# PowerPath.net
KiCad netlist of a schematic drawn in Altium Designer
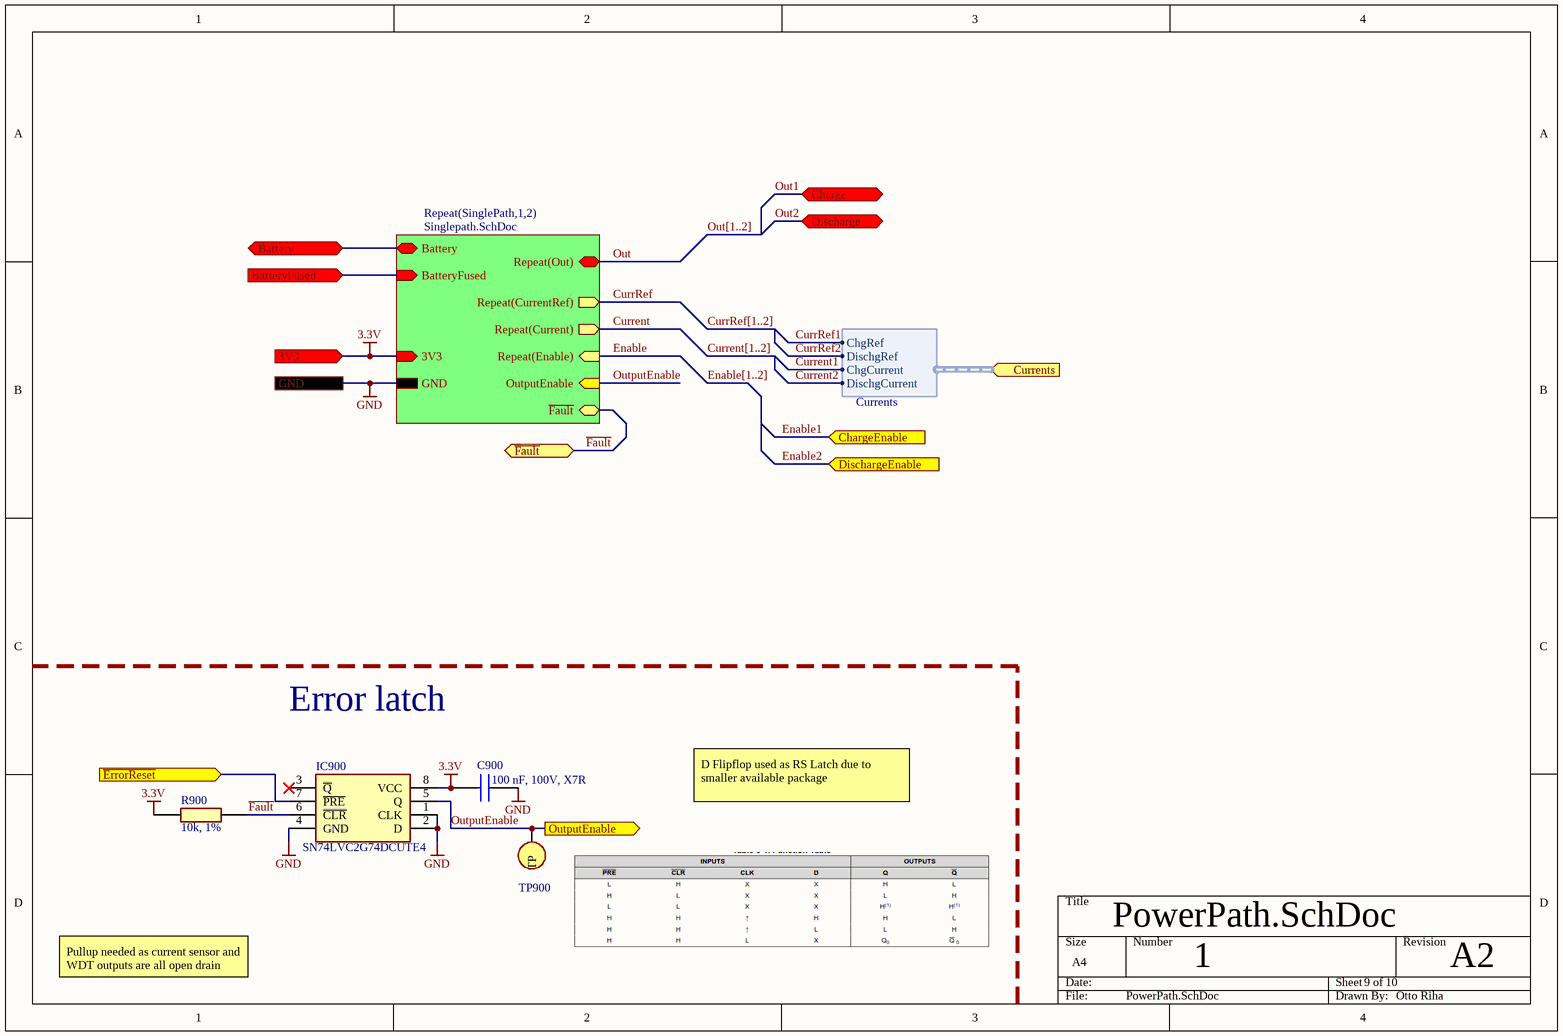
[diagram p0: PowerPath.SchDoc]

(export (version "E")
  (design (tool "Eeschema 10.0.6"))
  (components
    (comp (ref "C900")
      (value "100 nF, 100V, X7R")
      (footprint "SamacSys:MAJx16")
      (description "Capacitor 100nF, 100V, X7R")
      (fields
        (field (name "MANUFACTURER_PART_NUMBER") "MAJCH168BB7104KTEA01")
        (field (name "MOUSER PART NUMBER") "963-MAJCH168BB7104KT")
      )
      (libsource (lib "SamacSys") (part "MAJCH168BB7104KTEA01"))
    )
    (comp (ref "IC900")
      (value "SN74LVC2G74DCUTE4")
      (footprint "SamacSys:SOP50P310X90-8N")
      (description "Integrated Circuit")
      (fields (field (name "MOUSER PART NUMBER") "595-74LVC2G74DCUTE4"))
      (libsource (lib "SamacSys") (part "SN74LVC2G74DCUTE4"))
    )
    (comp (ref "R900")
      (value "10k, 1%")
      (footprint "SamacSys:RESC1608X50N")
      (description "Resistor 10k, 1%")
      (fields
        (field (name "MANUFACTURER_PART_NUMBER") "CRCW060310K0FKEI")
        (field (name "MOUSER PART NUMBER") "71-CRCW060310K0FKEI")
      )
      (libsource (lib "SamacSys") (part "CRCW060310K0FKEI"))
    )
    (comp (ref "TP900")
      (value "Testpoint")
      (footprint "Testpoint")
      (libsource (lib "SamacSys") (part "Testpoint"))
    )
  )
  (nets
    (net (code "20") (name "/OutputEnable") (class "Default")
      (node (ref "IC900") (pin "5") (pinfunction "Q_5") (pintype "passive"))
      (node (ref "TP900") (pin "1") (pinfunction "TP_1") (pintype "passive"))
    )
    (net (code "22") (name "/~{ErrorReset}") (class "Default")
      (node (ref "IC900") (pin "7") (pinfunction "~{PRE}_7") (pintype "passive"))
    )
    (net (code "23") (name "/~{Fault}") (class "Default")
      (node (ref "IC900") (pin "6") (pinfunction "~{CLR}_6") (pintype "passive"))
      (node (ref "R900") (pin "2") (pinfunction "2_2") (pintype "passive"))
    )
    (net (code "24") (name "3.3V") (class "Default")
      (node (ref "C900") (pin "1") (pinfunction "1_1") (pintype "passive"))
      (node (ref "IC900") (pin "8") (pinfunction "VCC_8") (pintype "passive"))
      (node (ref "R900") (pin "1") (pinfunction "1_1") (pintype "passive"))
    )
    (net (code "25") (name "GND") (class "Default")
      (node (ref "C900") (pin "2") (pinfunction "2_2") (pintype "passive"))
      (node (ref "IC900") (pin "1") (pinfunction "CLK_1") (pintype "passive"))
      (node (ref "IC900") (pin "2") (pinfunction "D_2") (pintype "passive"))
      (node (ref "IC900") (pin "4") (pinfunction "GND_4") (pintype "passive"))
    )
    (net (code "26") (name "unconnected-(IC900-~{Q}-Pad3)") (class "Default")
      (node (ref "IC900") (pin "3") (pinfunction "~{Q}_3") (pintype "passive+no_connect"))
    )
  )
)
